# JEDI_I2C_Bridge_v1_4.net
KiCad netlist of a schematic drawn in EAGLE
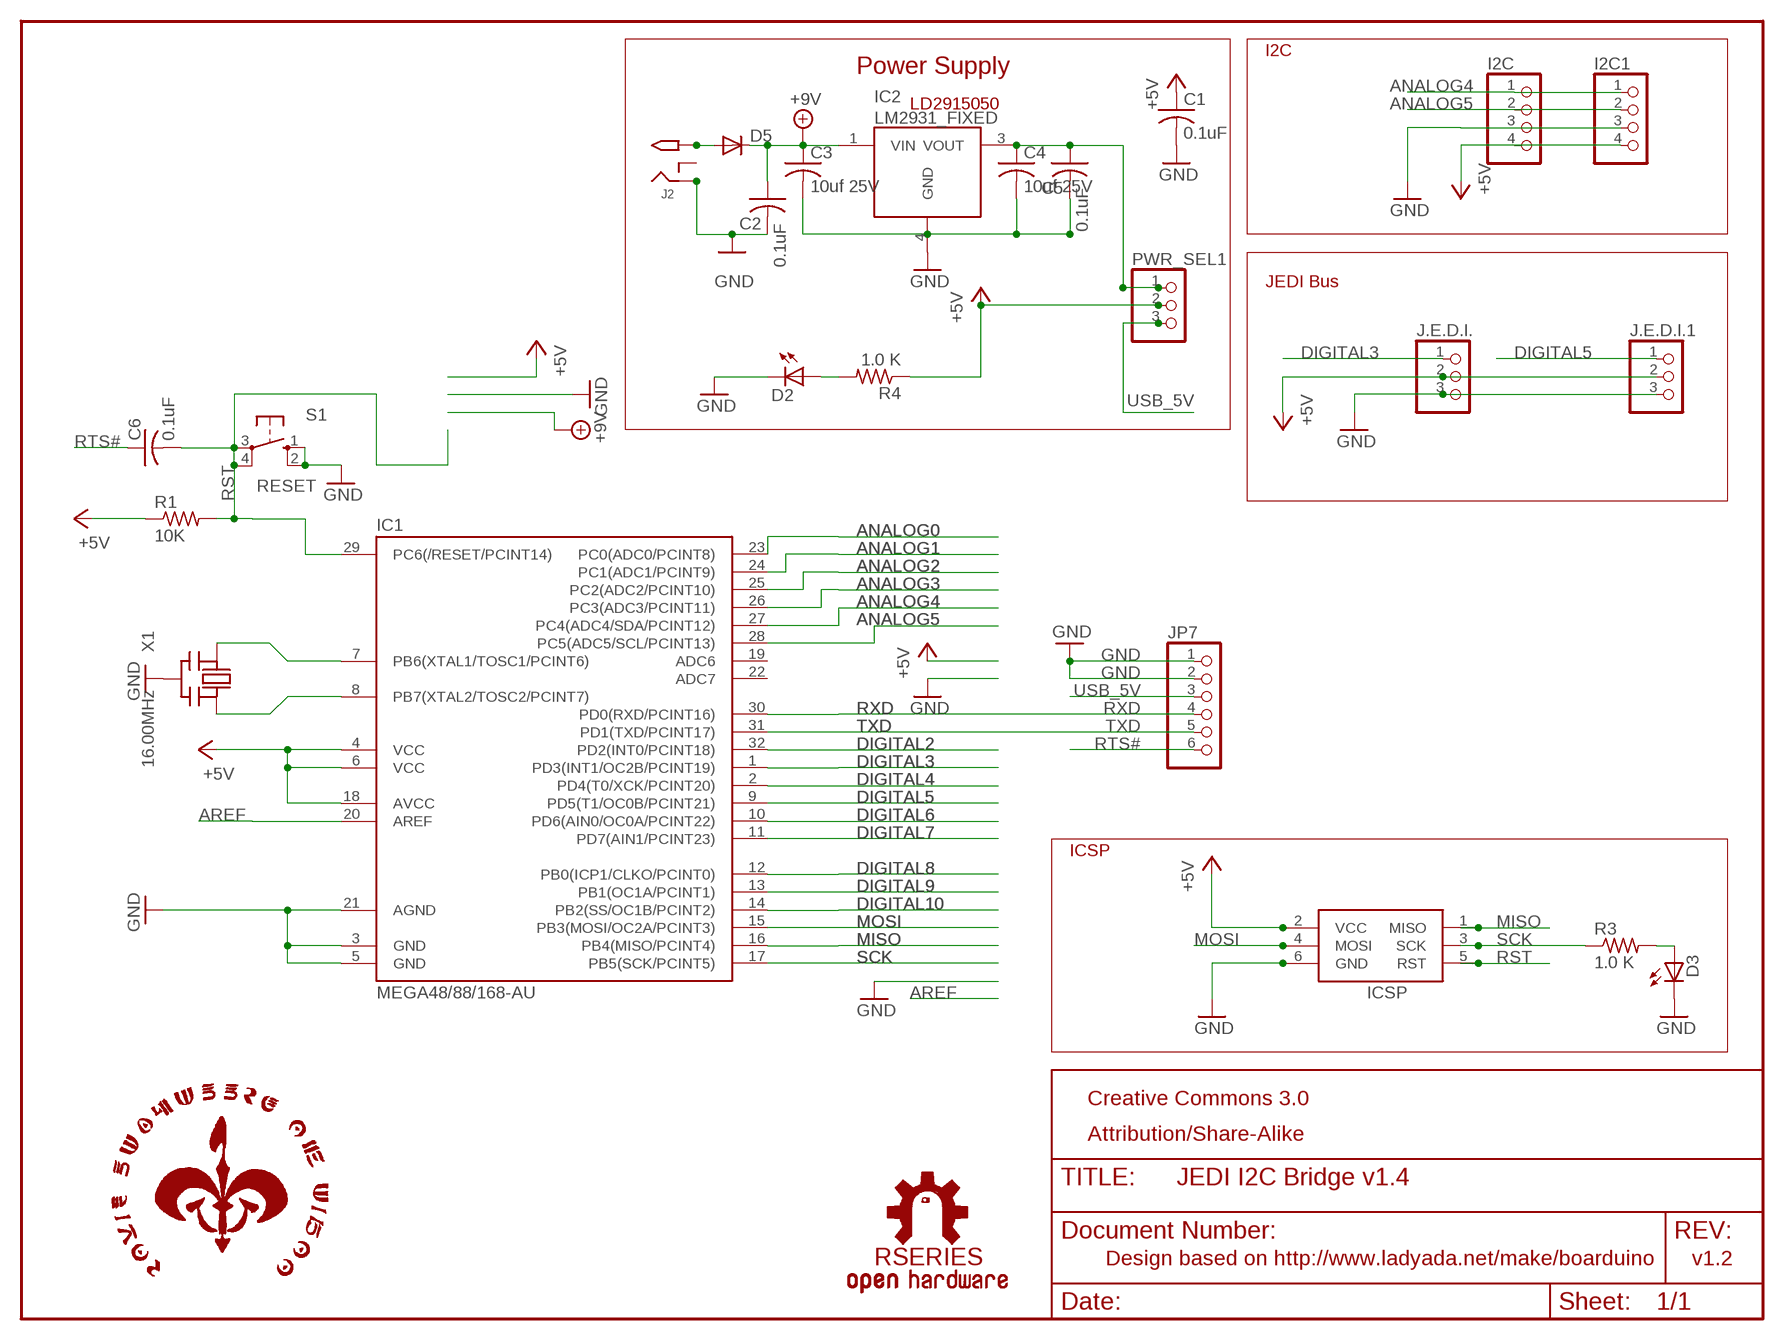
[diagram p0: schematic, sheet 1]

(export (version "E")
  (design (tool "Eeschema 10.0.6"))
  (components
    (comp (ref "C1")
      (value "0.1uF")
      (footprint "eagle-import:C1206K")
      (libsource (lib "eagle-import") (part "C-USC1206K"))
    )
    (comp (ref "C2")
      (value "0.1uF")
      (footprint "eagle-import:C1206K")
      (libsource (lib "eagle-import") (part "C-USC1206K"))
    )
    (comp (ref "C3")
      (value "10uf 25V")
      (footprint "eagle-import:C1206K")
      (libsource (lib "eagle-import") (part "rcl_C-USC1206K"))
    )
    (comp (ref "C4")
      (value "10uf 25V")
      (footprint "eagle-import:C1206K")
      (libsource (lib "eagle-import") (part "rcl_C-USC1206K"))
    )
    (comp (ref "C5")
      (value "0.1uF")
      (footprint "eagle-import:C1206K")
      (libsource (lib "eagle-import") (part "C-USC1206K"))
    )
    (comp (ref "C6")
      (value "0.1uF")
      (footprint "eagle-import:C1206K")
      (libsource (lib "eagle-import") (part "C-USC1206K"))
    )
    (comp (ref "D2")
      (value "LEDCHIPLED_1206")
      (footprint "eagle-import:CHIPLED_1206")
      (libsource (lib "eagle-import") (part "LEDCHIPLED_1206"))
    )
    (comp (ref "D3")
      (value "Green")
      (footprint "eagle-import:CHIPLED_1206")
      (libsource (lib "eagle-import") (part "LEDCHIPLED_1206"))
    )
    (comp (ref "D5")
      (value "DIODE-SMB")
      (footprint "eagle-import:SMB")
      (libsource (lib "eagle-import") (part "DIODE-SMB"))
    )
    (comp (ref "I2C")
      (value "PINHD-1X4CB")
      (footprint "eagle-import:1X04-CB")
      (libsource (lib "eagle-import") (part "PINHD-1X4CB"))
    )
    (comp (ref "I2C1")
      (value "PINHD-1X4CB")
      (footprint "eagle-import:1X04-CB")
      (libsource (lib "eagle-import") (part "PINHD-1X4CB"))
    )
    (comp (ref "IC1")
      (value "MEGA48/88/168-AU")
      (footprint "eagle-import:TQFP32-08")
      (libsource (lib "eagle-import") (part "MEGA48/88/168-AU"))
    )
    (comp (ref "IC2")
      (value "LM2931_FIXED")
      (footprint "eagle-import:DPAK")
      (libsource (lib "eagle-import") (part "LM2931_FIXED"))
    )
    (comp (ref "ICSP")
      (value "AVRISP-6")
      (footprint "eagle-import:AVRISP")
      (libsource (lib "eagle-import") (part "AVRISP-6"))
    )
    (comp (ref "J.E.D.I.")
      (value "PINHD-1X3")
      (footprint "eagle-import:1X03")
      (libsource (lib "eagle-import") (part "PINHD-1X3"))
    )
    (comp (ref "J.E.D.I.1")
      (value "PINHD-1X3")
      (footprint "eagle-import:1X03")
      (libsource (lib "eagle-import") (part "PINHD-1X3"))
    )
    (comp (ref "J2")
      (value "2.1MMJACK")
      (footprint "eagle-import:PJ-102A")
      (libsource (lib "eagle-import") (part "2.1MMJACK"))
    )
    (comp (ref "JP7")
      (value "PINHD-1X6CLEAN")
      (footprint "eagle-import:1X06-CLEAN")
      (libsource (lib "eagle-import") (part "PINHD-1X6CLEAN"))
    )
    (comp (ref "PWR_SEL1")
      (value "PINHD-1X3")
      (footprint "eagle-import:1X03")
      (libsource (lib "eagle-import") (part "PINHD-1X3"))
    )
    (comp (ref "R1")
      (value "10K")
      (footprint "eagle-import:R1206")
      (libsource (lib "eagle-import") (part "rcl-ez_R-US_R1206"))
    )
    (comp (ref "R3")
      (value "1.0 K")
      (footprint "eagle-import:M1206")
      (libsource (lib "eagle-import") (part "R-US_M1206"))
    )
    (comp (ref "R4")
      (value "1.0 K")
      (footprint "eagle-import:M1206")
      (libsource (lib "eagle-import") (part "R-US_M1206"))
    )
    (comp (ref "S1")
      (value "RESET")
      (footprint "eagle-import:B3F-10XX")
      (libsource (lib "eagle-import") (part "10-XX"))
    )
    (comp (ref "U$2")
      (value "RSERIES-OSHW-LOGOMEDIUM")
      (footprint "eagle-import:RSERIES-OSHW-LOGO-MEDIUM")
      (libsource (lib "eagle-import") (part "RSERIES-OSHW-LOGOMEDIUM"))
    )
    (comp (ref "U$3")
      (value "ROYAL-ENGINEERS-OF-NABOOSMALL")
      (footprint "eagle-import:ROYAL-ENGINEERS-OF-NABOO-SMALL")
      (libsource (lib "eagle-import") (part "ROYAL-ENGINEERS-OF-NABOOSMALL"))
    )
    (comp (ref "X1")
      (value "16.00MHz")
      (footprint "eagle-import:CERM_OSC")
      (libsource (lib "eagle-import") (part "CERMOSCILL"))
    )
  )
  (nets
    (net (code "1") (name "+5V") (class "Default")
      (node (ref "C1") (pin "1") (pinfunction "1_1") (pintype "passive"))
      (node (ref "I2C") (pin "4") (pinfunction "4_4") (pintype "passive"))
      (node (ref "I2C1") (pin "4") (pinfunction "4_4") (pintype "passive"))
      (node (ref "IC1") (pin "18") (pinfunction "AVCC_18") (pintype "passive"))
      (node (ref "IC1") (pin "4") (pinfunction "VCC_4") (pintype "power_in"))
      (node (ref "IC1") (pin "6") (pinfunction "VCC_6") (pintype "power_in"))
      (node (ref "ICSP") (pin "2") (pinfunction "VCC_2") (pintype "power_in"))
      (node (ref "J.E.D.I.") (pin "2") (pinfunction "2_2") (pintype "passive"))
      (node (ref "J.E.D.I.1") (pin "2") (pinfunction "2_2") (pintype "passive"))
      (node (ref "PWR_SEL1") (pin "2") (pinfunction "2_2") (pintype "passive"))
      (node (ref "R1") (pin "1") (pinfunction "1_1") (pintype "passive"))
      (node (ref "R4") (pin "1") (pinfunction "1_1") (pintype "passive"))
    )
    (net (code "2") (name "+9V") (class "Default")
      (node (ref "C2") (pin "1") (pinfunction "1_1") (pintype "passive"))
      (node (ref "C3") (pin "1") (pinfunction "1_1") (pintype "passive"))
      (node (ref "D5") (pin "C") (pinfunction "C_C") (pintype "passive"))
      (node (ref "IC2") (pin "1") (pinfunction "VIN_1") (pintype "bidirectional"))
    )
    (net (code "3") (name "/ANALOG0") (class "Default")
      (node (ref "IC1") (pin "23") (pinfunction "PC0(ADC0/PCINT8)_23") (pintype "bidirectional"))
    )
    (net (code "4") (name "/ANALOG1") (class "Default")
      (node (ref "IC1") (pin "24") (pinfunction "PC1(ADC1/PCINT9)_24") (pintype "bidirectional"))
    )
    (net (code "5") (name "/ANALOG2") (class "Default")
      (node (ref "IC1") (pin "25") (pinfunction "PC2(ADC2/PCINT10)_25") (pintype "bidirectional"))
    )
    (net (code "6") (name "/ANALOG3") (class "Default")
      (node (ref "IC1") (pin "26") (pinfunction "PC3(ADC3/PCINT11)_26") (pintype "bidirectional"))
    )
    (net (code "7") (name "/ANALOG4") (class "Default")
      (node (ref "I2C") (pin "1") (pinfunction "1_1") (pintype "passive"))
      (node (ref "I2C1") (pin "1") (pinfunction "1_1") (pintype "passive"))
      (node (ref "IC1") (pin "27") (pinfunction "PC4(ADC4/SDA/PCINT12)_27") (pintype "bidirectional"))
    )
    (net (code "8") (name "/ANALOG5") (class "Default")
      (node (ref "I2C") (pin "2") (pinfunction "2_2") (pintype "passive"))
      (node (ref "I2C1") (pin "2") (pinfunction "2_2") (pintype "passive"))
      (node (ref "IC1") (pin "28") (pinfunction "PC5(ADC5/SCL/PCINT13)_28") (pintype "bidirectional"))
    )
    (net (code "9") (name "/AREF") (class "Default")
      (node (ref "IC1") (pin "20") (pinfunction "AREF_20") (pintype "passive"))
    )
    (net (code "10") (name "/DIGITAL2") (class "Default")
      (node (ref "IC1") (pin "32") (pinfunction "PD2(INT0/PCINT18)_32") (pintype "bidirectional"))
    )
    (net (code "11") (name "/DIGITAL3") (class "Default")
      (node (ref "IC1") (pin "1") (pinfunction "PD3(INT1/OC2B/PCINT19)_1") (pintype "bidirectional"))
      (node (ref "J.E.D.I.") (pin "1") (pinfunction "1_1") (pintype "passive"))
    )
    (net (code "12") (name "/DIGITAL4") (class "Default")
      (node (ref "IC1") (pin "2") (pinfunction "PD4(T0/XCK/PCINT20)_2") (pintype "bidirectional"))
    )
    (net (code "13") (name "/DIGITAL5") (class "Default")
      (node (ref "IC1") (pin "9") (pinfunction "PD5(T1/OC0B/PCINT21)_9") (pintype "bidirectional"))
      (node (ref "J.E.D.I.1") (pin "1") (pinfunction "1_1") (pintype "passive"))
    )
    (net (code "14") (name "/DIGITAL6") (class "Default")
      (node (ref "IC1") (pin "10") (pinfunction "PD6(AIN0/OC0A/PCINT22)_10") (pintype "bidirectional"))
    )
    (net (code "15") (name "/DIGITAL7") (class "Default")
      (node (ref "IC1") (pin "11") (pinfunction "PD7(AIN1/PCINT23)_11") (pintype "bidirectional"))
    )
    (net (code "16") (name "/DIGITAL8") (class "Default")
      (node (ref "IC1") (pin "12") (pinfunction "PB0(ICP1/CLKO/PCINT0)_12") (pintype "bidirectional"))
    )
    (net (code "17") (name "/DIGITAL9") (class "Default")
      (node (ref "IC1") (pin "13") (pinfunction "PB1(OC1A/PCINT1)_13") (pintype "bidirectional"))
    )
    (net (code "18") (name "/DIGITAL10") (class "Default")
      (node (ref "IC1") (pin "14") (pinfunction "PB2(SS/OC1B/PCINT2)_14") (pintype "bidirectional"))
    )
    (net (code "19") (name "/MISO") (class "Default")
      (node (ref "IC1") (pin "16") (pinfunction "PB4(MISO/PCINT4)_16") (pintype "bidirectional"))
      (node (ref "ICSP") (pin "1") (pinfunction "MISO_1") (pintype "input"))
    )
    (net (code "20") (name "/MOSI") (class "Default")
      (node (ref "IC1") (pin "15") (pinfunction "PB3(MOSI/OC2A/PCINT3)_15") (pintype "bidirectional"))
      (node (ref "ICSP") (pin "4") (pinfunction "MOSI_4") (pintype "output"))
    )
    (net (code "21") (name "/RST") (class "Default")
      (node (ref "C6") (pin "2") (pinfunction "2_2") (pintype "passive"))
      (node (ref "IC1") (pin "29") (pinfunction "PC6(/RESET/PCINT14)_29") (pintype "bidirectional"))
      (node (ref "ICSP") (pin "5") (pinfunction "RST_5") (pintype "output"))
      (node (ref "R1") (pin "2") (pinfunction "2_2") (pintype "passive"))
      (node (ref "S1") (pin "3") (pinfunction "P_3") (pintype "passive"))
      (node (ref "S1") (pin "4") (pinfunction "P1_4") (pintype "passive"))
    )
    (net (code "22") (name "/RTS#") (class "Default")
      (node (ref "C6") (pin "1") (pinfunction "1_1") (pintype "passive"))
      (node (ref "JP7") (pin "6") (pinfunction "6_6") (pintype "passive"))
    )
    (net (code "23") (name "/RXD") (class "Default")
      (node (ref "IC1") (pin "30") (pinfunction "PD0(RXD/PCINT16)_30") (pintype "bidirectional"))
      (node (ref "JP7") (pin "4") (pinfunction "4_4") (pintype "passive"))
    )
    (net (code "24") (name "/SCK") (class "Default")
      (node (ref "IC1") (pin "17") (pinfunction "PB5(SCK/PCINT5)_17") (pintype "bidirectional"))
      (node (ref "ICSP") (pin "3") (pinfunction "SCK_3") (pintype "output"))
      (node (ref "R3") (pin "1") (pinfunction "1_1") (pintype "passive"))
    )
    (net (code "25") (name "/TXD") (class "Default")
      (node (ref "IC1") (pin "31") (pinfunction "PD1(TXD/PCINT17)_31") (pintype "bidirectional"))
      (node (ref "JP7") (pin "5") (pinfunction "5_5") (pintype "passive"))
    )
    (net (code "26") (name "/USB_5V") (class "Default")
      (node (ref "JP7") (pin "3") (pinfunction "3_3") (pintype "passive"))
      (node (ref "PWR_SEL1") (pin "3") (pinfunction "3_3") (pintype "passive"))
    )
    (net (code "27") (name "GND") (class "Default")
      (node (ref "C1") (pin "2") (pinfunction "2_2") (pintype "passive"))
      (node (ref "C2") (pin "2") (pinfunction "2_2") (pintype "passive"))
      (node (ref "D2") (pin "C") (pinfunction "C_C") (pintype "passive"))
      (node (ref "D3") (pin "C") (pinfunction "C_C") (pintype "passive"))
      (node (ref "I2C") (pin "3") (pinfunction "3_3") (pintype "passive"))
      (node (ref "I2C1") (pin "3") (pinfunction "3_3") (pintype "passive"))
      (node (ref "IC1") (pin "21") (pinfunction "AGND_21") (pintype "power_in"))
      (node (ref "IC1") (pin "3") (pinfunction "GND_3") (pintype "power_in"))
      (node (ref "IC1") (pin "5") (pinfunction "GND_5") (pintype "power_in"))
      (node (ref "IC2") (pin "4") (pinfunction "GND_4") (pintype "bidirectional"))
      (node (ref "ICSP") (pin "6") (pinfunction "GND_6") (pintype "power_in"))
      (node (ref "J.E.D.I.") (pin "3") (pinfunction "3_3") (pintype "passive"))
      (node (ref "J.E.D.I.1") (pin "3") (pinfunction "3_3") (pintype "passive"))
      (node (ref "J2") (pin "RING") (pinfunction "RING_RING") (pintype "bidirectional"))
      (node (ref "JP7") (pin "1") (pinfunction "1_1") (pintype "passive"))
      (node (ref "JP7") (pin "2") (pinfunction "2_2") (pintype "passive"))
      (node (ref "S1") (pin "1") (pinfunction "S_1") (pintype "passive"))
      (node (ref "S1") (pin "2") (pinfunction "S1_2") (pintype "passive"))
      (node (ref "X1") (pin "P$2") (pinfunction "GND_P$2") (pintype "bidirectional"))
    )
    (net (code "28") (name "Net-(C3-Pad2)") (class "Default")
      (node (ref "C3") (pin "2") (pinfunction "2_2") (pintype "passive"))
      (node (ref "C4") (pin "2") (pinfunction "2_2") (pintype "passive"))
      (node (ref "C5") (pin "2") (pinfunction "2_2") (pintype "passive"))
    )
    (net (code "29") (name "Net-(D2-PadA)") (class "Default")
      (node (ref "D2") (pin "A") (pinfunction "A_A") (pintype "passive"))
      (node (ref "R4") (pin "2") (pinfunction "2_2") (pintype "passive"))
    )
    (net (code "30") (name "Net-(D3-PadA)") (class "Default")
      (node (ref "D3") (pin "A") (pinfunction "A_A") (pintype "passive"))
      (node (ref "R3") (pin "2") (pinfunction "2_2") (pintype "passive"))
    )
    (net (code "31") (name "Net-(D5-PadA)") (class "Default")
      (node (ref "D5") (pin "A") (pinfunction "A_A") (pintype "passive"))
      (node (ref "J2") (pin "TIP") (pinfunction "TIP_TIP") (pintype "bidirectional"))
    )
    (net (code "32") (name "Net-(IC1-PB6(XTAL1{slash}TOSC1{slash}PCINT6))") (class "Default")
      (node (ref "IC1") (pin "7") (pinfunction "PB6(XTAL1/TOSC1/PCINT6)_7") (pintype "bidirectional"))
      (node (ref "X1") (pin "P$1") (pinfunction "IN_P$1") (pintype "bidirectional"))
    )
    (net (code "33") (name "Net-(IC1-PB7(XTAL2{slash}TOSC2{slash}PCINT7))") (class "Default")
      (node (ref "IC1") (pin "8") (pinfunction "PB7(XTAL2/TOSC2/PCINT7)_8") (pintype "bidirectional"))
      (node (ref "X1") (pin "P$3") (pinfunction "OUT_P$3") (pintype "bidirectional"))
    )
    (net (code "34") (name "Net-(IC2-VOUT)") (class "Default")
      (node (ref "C4") (pin "1") (pinfunction "1_1") (pintype "passive"))
      (node (ref "C5") (pin "1") (pinfunction "1_1") (pintype "passive"))
      (node (ref "IC2") (pin "3") (pinfunction "VOUT_3") (pintype "bidirectional"))
      (node (ref "PWR_SEL1") (pin "1") (pinfunction "1_1") (pintype "passive"))
    )
    (net (code "35") (name "unconnected-(IC1-ADC6-Pad19)") (class "Default")
      (node (ref "IC1") (pin "19") (pinfunction "ADC6_19") (pintype "passive"))
    )
    (net (code "36") (name "unconnected-(IC1-ADC7-Pad22)") (class "Default")
      (node (ref "IC1") (pin "22") (pinfunction "ADC7_22") (pintype "passive"))
    )
    (net (code "37") (name "unconnected-(J2-PadRING_SW)") (class "Default")
      (node (ref "J2") (pin "RING_SW") (pinfunction "RING_SW_RING_SW") (pintype "bidirectional"))
    )
  )
)
